# ProcessorBoard.net
KiCad netlist of a schematic drawn in EAGLE
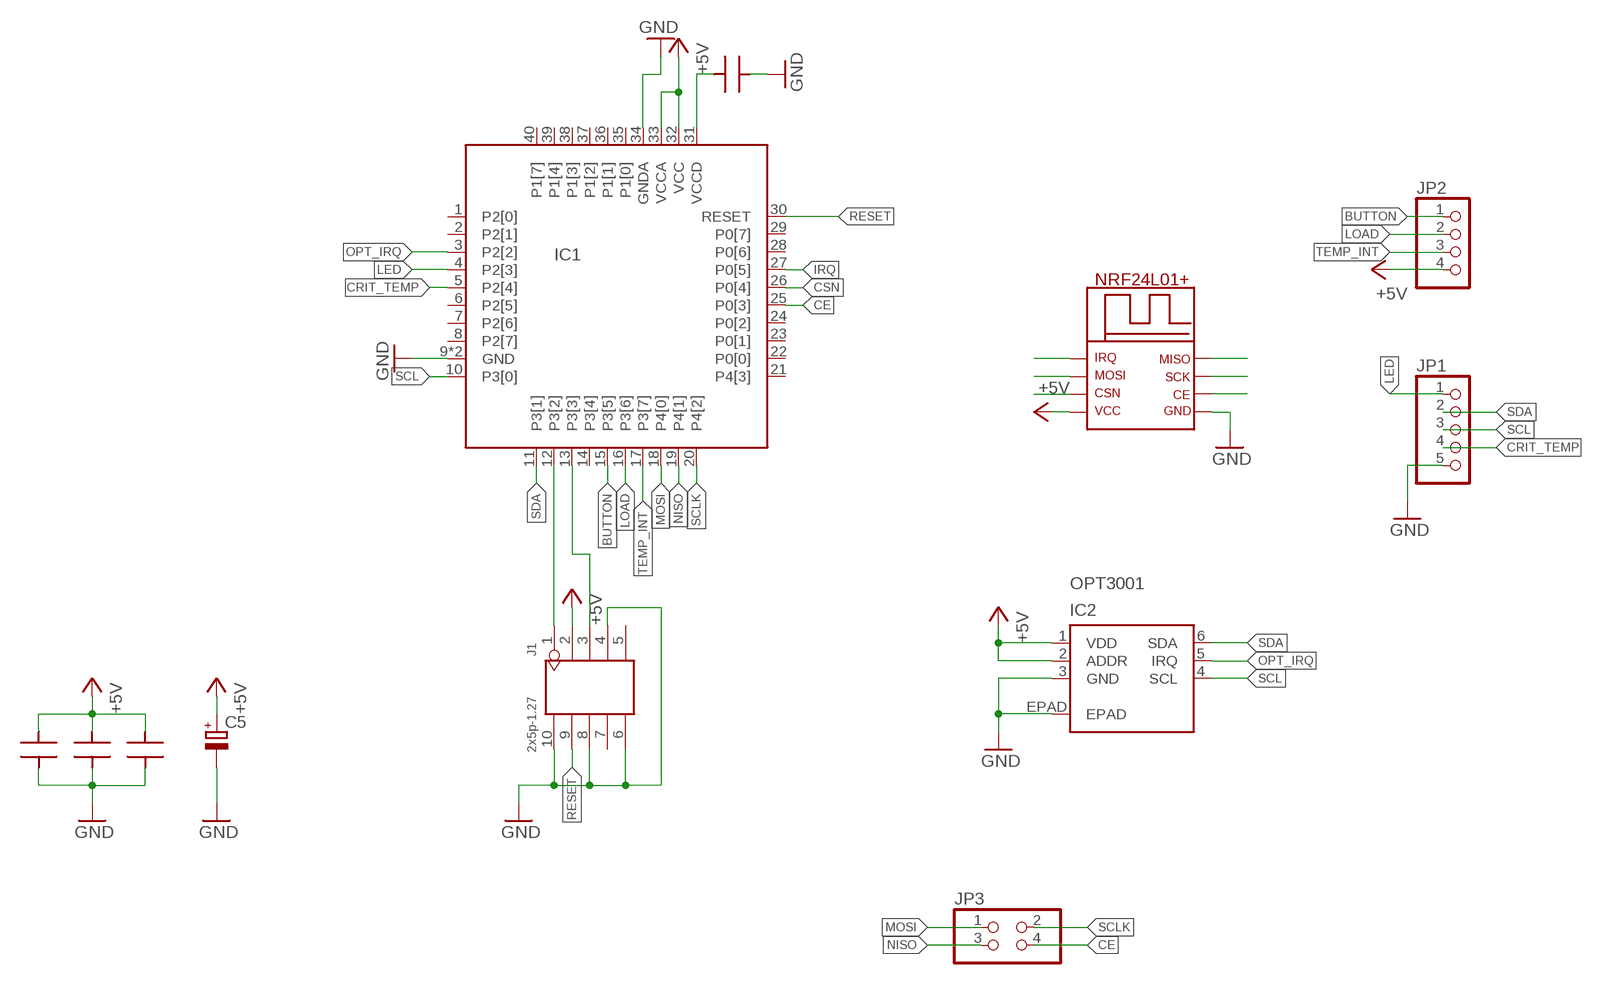
[diagram p0: schematic, sheet 1]

(export (version "E")
  (design (tool "Eeschema 10.0.6"))
  (components
    (comp (ref "C1")
      (value "CAP0603")
      (footprint "eagle-import:C0603")
      (libsource (lib "eagle-import") (part "CAP0603"))
    )
    (comp (ref "C2")
      (value "CAP0603")
      (footprint "eagle-import:C0603")
      (libsource (lib "eagle-import") (part "CAP0603"))
    )
    (comp (ref "C3")
      (value "CAP0603")
      (footprint "eagle-import:C0603")
      (libsource (lib "eagle-import") (part "CAP0603"))
    )
    (comp (ref "C4")
      (value "CAP0603")
      (footprint "eagle-import:C0603")
      (libsource (lib "eagle-import") (part "CAP0603"))
    )
    (comp (ref "C5")
      (value "CPOL-EUSMCA")
      (footprint "eagle-import:SMC_A")
      (libsource (lib "eagle-import") (part "CPOL-EUSMCA"))
    )
    (comp (ref "IC1")
      (value "CY8C4245-LQI-LONG")
      (footprint "eagle-import:QFN40-LONG")
      (libsource (lib "eagle-import") (part "CY8C4245-LQI-LONG"))
    )
    (comp (ref "IC2")
      (value "OPT3001")
      (footprint "eagle-import:USON6")
      (libsource (lib "eagle-import") (part "OPT3001"))
    )
    (comp (ref "J1")
      (value "2x5p-1.27")
      (footprint "eagle-import:H2X5-SMD-1.27")
      (fields (field (name "MPN") "F243-1109A0BMUB2"))
      (libsource (lib "eagle-import") (part "SMD-BLACK-MALE-HEADER(2X5P-1.27)"))
    )
    (comp (ref "JP1")
      (value "PINHD-1X5")
      (footprint "eagle-import:1X05")
      (libsource (lib "eagle-import") (part "PINHD-1X5"))
    )
    (comp (ref "JP2")
      (value "PINHD-1X4")
      (footprint "eagle-import:1X04")
      (libsource (lib "eagle-import") (part "PINHD-1X4"))
    )
    (comp (ref "JP3")
      (value "PINHD-2X2")
      (footprint "eagle-import:2X02")
      (libsource (lib "eagle-import") (part "PINHD-2X2"))
    )
    (comp (ref "U$1")
      (value "NRF24")
      (footprint "eagle-import:NRF")
      (libsource (lib "eagle-import") (part "NRF24"))
    )
  )
  (nets
    (net (code "1") (name "+5V") (class "Default")
      (node (ref "C2") (pin "2") (pinfunction "P$2_2") (pintype "bidirectional"))
      (node (ref "C3") (pin "2") (pinfunction "P$2_2") (pintype "bidirectional"))
      (node (ref "C4") (pin "2") (pinfunction "P$2_2") (pintype "bidirectional"))
      (node (ref "C5") (pin "+") (pinfunction "+_+") (pintype "passive"))
      (node (ref "IC1") (pin "32") (pinfunction "VCC_32") (pintype "power_in"))
      (node (ref "IC1") (pin "33") (pinfunction "VCCA_33") (pintype "power_in"))
      (node (ref "IC2") (pin "1") (pinfunction "VDD_1") (pintype "power_in"))
      (node (ref "IC2") (pin "2") (pinfunction "ADDR_2") (pintype "bidirectional"))
      (node (ref "J1") (pin "2") (pinfunction "2_2") (pintype "bidirectional"))
      (node (ref "JP2") (pin "4") (pinfunction "4_4") (pintype "passive"))
      (node (ref "U$1") (pin "VCC") (pinfunction "VCC_VCC") (pintype "bidirectional"))
    )
    (net (code "2") (name "BUTTON") (class "Default")
      (node (ref "IC1") (pin "15") (pinfunction "P3[5]_15") (pintype "bidirectional"))
      (node (ref "JP2") (pin "1") (pinfunction "1_1") (pintype "passive"))
    )
    (net (code "3") (name "CE") (class "Default")
      (node (ref "IC1") (pin "25") (pinfunction "P0[3]_25") (pintype "bidirectional"))
      (node (ref "JP3") (pin "4") (pinfunction "4_4") (pintype "passive"))
      (node (ref "U$1") (pin "CE") (pinfunction "CE_CE") (pintype "bidirectional"))
    )
    (net (code "4") (name "CRIT_TEMP") (class "Default")
      (node (ref "IC1") (pin "5") (pinfunction "P2[4]_5") (pintype "bidirectional"))
      (node (ref "JP1") (pin "4") (pinfunction "4_4") (pintype "passive"))
    )
    (net (code "5") (name "CSN") (class "Default")
      (node (ref "IC1") (pin "26") (pinfunction "P0[4]_26") (pintype "bidirectional"))
      (node (ref "U$1") (pin "CSN") (pinfunction "CSN_CSN") (pintype "bidirectional"))
    )
    (net (code "6") (name "GND") (class "Default")
      (node (ref "C1") (pin "2") (pinfunction "P$2_2") (pintype "bidirectional"))
      (node (ref "C2") (pin "1") (pinfunction "P$1_1") (pintype "bidirectional"))
      (node (ref "C3") (pin "1") (pinfunction "P$1_1") (pintype "bidirectional"))
      (node (ref "C4") (pin "1") (pinfunction "P$1_1") (pintype "bidirectional"))
      (node (ref "C5") (pin "-") (pinfunction "-_-") (pintype "passive"))
      (node (ref "IC1") (pin "34") (pinfunction "GNDA_34") (pintype "power_in"))
      (node (ref "IC1") (pin "41") (pinfunction "GND_41") (pintype "power_in"))
      (node (ref "IC1") (pin "9") (pinfunction "GND_9") (pintype "power_in"))
      (node (ref "IC2") (pin "3") (pinfunction "GND_3") (pintype "power_in"))
      (node (ref "IC2") (pin "EPAD") (pinfunction "EPAD_EPAD") (pintype "bidirectional"))
      (node (ref "J1") (pin "10") (pinfunction "10_10") (pintype "bidirectional"))
      (node (ref "J1") (pin "4") (pinfunction "4_4") (pintype "bidirectional"))
      (node (ref "J1") (pin "6") (pinfunction "6_6") (pintype "bidirectional"))
      (node (ref "J1") (pin "8") (pinfunction "8_8") (pintype "bidirectional"))
      (node (ref "JP1") (pin "5") (pinfunction "5_5") (pintype "passive"))
      (node (ref "U$1") (pin "GND") (pinfunction "GND_GND") (pintype "bidirectional"))
    )
    (net (code "7") (name "IRQ") (class "Default")
      (node (ref "IC1") (pin "27") (pinfunction "P0[5]_27") (pintype "bidirectional"))
      (node (ref "U$1") (pin "IRQ") (pinfunction "IRQ_IRQ") (pintype "bidirectional"))
    )
    (net (code "8") (name "LED") (class "Default")
      (node (ref "IC1") (pin "4") (pinfunction "P2[3]_4") (pintype "bidirectional"))
      (node (ref "JP1") (pin "1") (pinfunction "1_1") (pintype "passive"))
    )
    (net (code "9") (name "LOAD") (class "Default")
      (node (ref "IC1") (pin "16") (pinfunction "P3[6]_16") (pintype "bidirectional"))
      (node (ref "JP2") (pin "2") (pinfunction "2_2") (pintype "passive"))
    )
    (net (code "10") (name "MOSI") (class "Default")
      (node (ref "IC1") (pin "18") (pinfunction "P4[0]_18") (pintype "bidirectional"))
      (node (ref "JP3") (pin "1") (pinfunction "1_1") (pintype "passive"))
      (node (ref "U$1") (pin "MOSI") (pinfunction "MOSI_MOSI") (pintype "bidirectional"))
    )
    (net (code "11") (name "NISO") (class "Default")
      (node (ref "IC1") (pin "19") (pinfunction "P4[1]_19") (pintype "bidirectional"))
      (node (ref "JP3") (pin "3") (pinfunction "3_3") (pintype "passive"))
      (node (ref "U$1") (pin "MISO") (pinfunction "MISO_MISO") (pintype "bidirectional"))
    )
    (net (code "12") (name "Net-(C1-P$1)") (class "Default")
      (node (ref "C1") (pin "1") (pinfunction "P$1_1") (pintype "bidirectional"))
      (node (ref "IC1") (pin "31") (pinfunction "VCCD_31") (pintype "power_in"))
    )
    (net (code "13") (name "Net-(IC1-P3[2])") (class "Default")
      (node (ref "IC1") (pin "12") (pinfunction "P3[2]_12") (pintype "bidirectional"))
      (node (ref "J1") (pin "1") (pinfunction "1_1") (pintype "bidirectional"))
    )
    (net (code "14") (name "Net-(IC1-P3[3])") (class "Default")
      (node (ref "IC1") (pin "13") (pinfunction "P3[3]_13") (pintype "bidirectional"))
      (node (ref "J1") (pin "3") (pinfunction "3_3") (pintype "bidirectional"))
    )
    (net (code "15") (name "OPT_IRQ") (class "Default")
      (node (ref "IC1") (pin "3") (pinfunction "P2[2]_3") (pintype "bidirectional"))
      (node (ref "IC2") (pin "5") (pinfunction "IRQ_5") (pintype "bidirectional"))
    )
    (net (code "16") (name "RESET") (class "Default")
      (node (ref "IC1") (pin "30") (pinfunction "RESET_30") (pintype "input"))
      (node (ref "J1") (pin "9") (pinfunction "9_9") (pintype "bidirectional"))
    )
    (net (code "17") (name "SCL") (class "Default")
      (node (ref "IC1") (pin "10") (pinfunction "P3[0]_10") (pintype "bidirectional"))
      (node (ref "IC2") (pin "4") (pinfunction "SCL_4") (pintype "bidirectional"))
      (node (ref "JP1") (pin "3") (pinfunction "3_3") (pintype "passive"))
    )
    (net (code "18") (name "SCLK") (class "Default")
      (node (ref "IC1") (pin "20") (pinfunction "P4[2]_20") (pintype "bidirectional"))
      (node (ref "JP3") (pin "2") (pinfunction "2_2") (pintype "passive"))
      (node (ref "U$1") (pin "SCK") (pinfunction "SCK_SCK") (pintype "bidirectional"))
    )
    (net (code "19") (name "SDA") (class "Default")
      (node (ref "IC1") (pin "11") (pinfunction "P3[1]_11") (pintype "bidirectional"))
      (node (ref "IC2") (pin "6") (pinfunction "SDA_6") (pintype "bidirectional"))
      (node (ref "JP1") (pin "2") (pinfunction "2_2") (pintype "passive"))
    )
    (net (code "20") (name "TEMP_INT") (class "Default")
      (node (ref "IC1") (pin "17") (pinfunction "P3[7]_17") (pintype "bidirectional"))
      (node (ref "JP2") (pin "3") (pinfunction "3_3") (pintype "passive"))
    )
    (net (code "21") (name "unconnected-(IC1-P0[0]-Pad22)") (class "Default")
      (node (ref "IC1") (pin "22") (pinfunction "P0[0]_22") (pintype "bidirectional"))
    )
    (net (code "22") (name "unconnected-(IC1-P0[1]-Pad23)") (class "Default")
      (node (ref "IC1") (pin "23") (pinfunction "P0[1]_23") (pintype "bidirectional"))
    )
    (net (code "23") (name "unconnected-(IC1-P0[2]-Pad24)") (class "Default")
      (node (ref "IC1") (pin "24") (pinfunction "P0[2]_24") (pintype "bidirectional"))
    )
    (net (code "24") (name "unconnected-(IC1-P0[6]-Pad28)") (class "Default")
      (node (ref "IC1") (pin "28") (pinfunction "P0[6]_28") (pintype "bidirectional"))
    )
    (net (code "25") (name "unconnected-(IC1-P0[7]-Pad29)") (class "Default")
      (node (ref "IC1") (pin "29") (pinfunction "P0[7]_29") (pintype "bidirectional"))
    )
    (net (code "26") (name "unconnected-(IC1-P1[0]-Pad35)") (class "Default")
      (node (ref "IC1") (pin "35") (pinfunction "P1[0]_35") (pintype "bidirectional"))
    )
    (net (code "27") (name "unconnected-(IC1-P1[1]-Pad36)") (class "Default")
      (node (ref "IC1") (pin "36") (pinfunction "P1[1]_36") (pintype "bidirectional"))
    )
    (net (code "28") (name "unconnected-(IC1-P1[2]-Pad37)") (class "Default")
      (node (ref "IC1") (pin "37") (pinfunction "P1[2]_37") (pintype "bidirectional"))
    )
    (net (code "29") (name "unconnected-(IC1-P1[3]-Pad38)") (class "Default")
      (node (ref "IC1") (pin "38") (pinfunction "P1[3]_38") (pintype "bidirectional"))
    )
    (net (code "30") (name "unconnected-(IC1-P1[4]-Pad39)") (class "Default")
      (node (ref "IC1") (pin "39") (pinfunction "P1[4]_39") (pintype "bidirectional"))
    )
    (net (code "31") (name "unconnected-(IC1-P1[7]-Pad40)") (class "Default")
      (node (ref "IC1") (pin "40") (pinfunction "P1[7]_40") (pintype "bidirectional"))
    )
    (net (code "32") (name "unconnected-(IC1-P2[0]-Pad1)") (class "Default")
      (node (ref "IC1") (pin "1") (pinfunction "P2[0]_1") (pintype "bidirectional"))
    )
    (net (code "33") (name "unconnected-(IC1-P2[1]-Pad2)") (class "Default")
      (node (ref "IC1") (pin "2") (pinfunction "P2[1]_2") (pintype "bidirectional"))
    )
    (net (code "34") (name "unconnected-(IC1-P2[5]-Pad6)") (class "Default")
      (node (ref "IC1") (pin "6") (pinfunction "P2[5]_6") (pintype "bidirectional"))
    )
    (net (code "35") (name "unconnected-(IC1-P2[6]-Pad7)") (class "Default")
      (node (ref "IC1") (pin "7") (pinfunction "P2[6]_7") (pintype "bidirectional"))
    )
    (net (code "36") (name "unconnected-(IC1-P2[7]-Pad8)") (class "Default")
      (node (ref "IC1") (pin "8") (pinfunction "P2[7]_8") (pintype "bidirectional"))
    )
    (net (code "37") (name "unconnected-(IC1-P3[4]-Pad14)") (class "Default")
      (node (ref "IC1") (pin "14") (pinfunction "P3[4]_14") (pintype "bidirectional"))
    )
    (net (code "38") (name "unconnected-(IC1-P4[3]-Pad21)") (class "Default")
      (node (ref "IC1") (pin "21") (pinfunction "P4[3]_21") (pintype "bidirectional"))
    )
    (net (code "39") (name "unconnected-(J1-Pad5)") (class "Default")
      (node (ref "J1") (pin "5") (pinfunction "5_5") (pintype "bidirectional"))
    )
    (net (code "40") (name "unconnected-(J1-Pad7)") (class "Default")
      (node (ref "J1") (pin "7") (pinfunction "7_7") (pintype "bidirectional"))
    )
  )
)
